# Main_SCH.net
KiCad netlist of a schematic drawn in Altium Designer
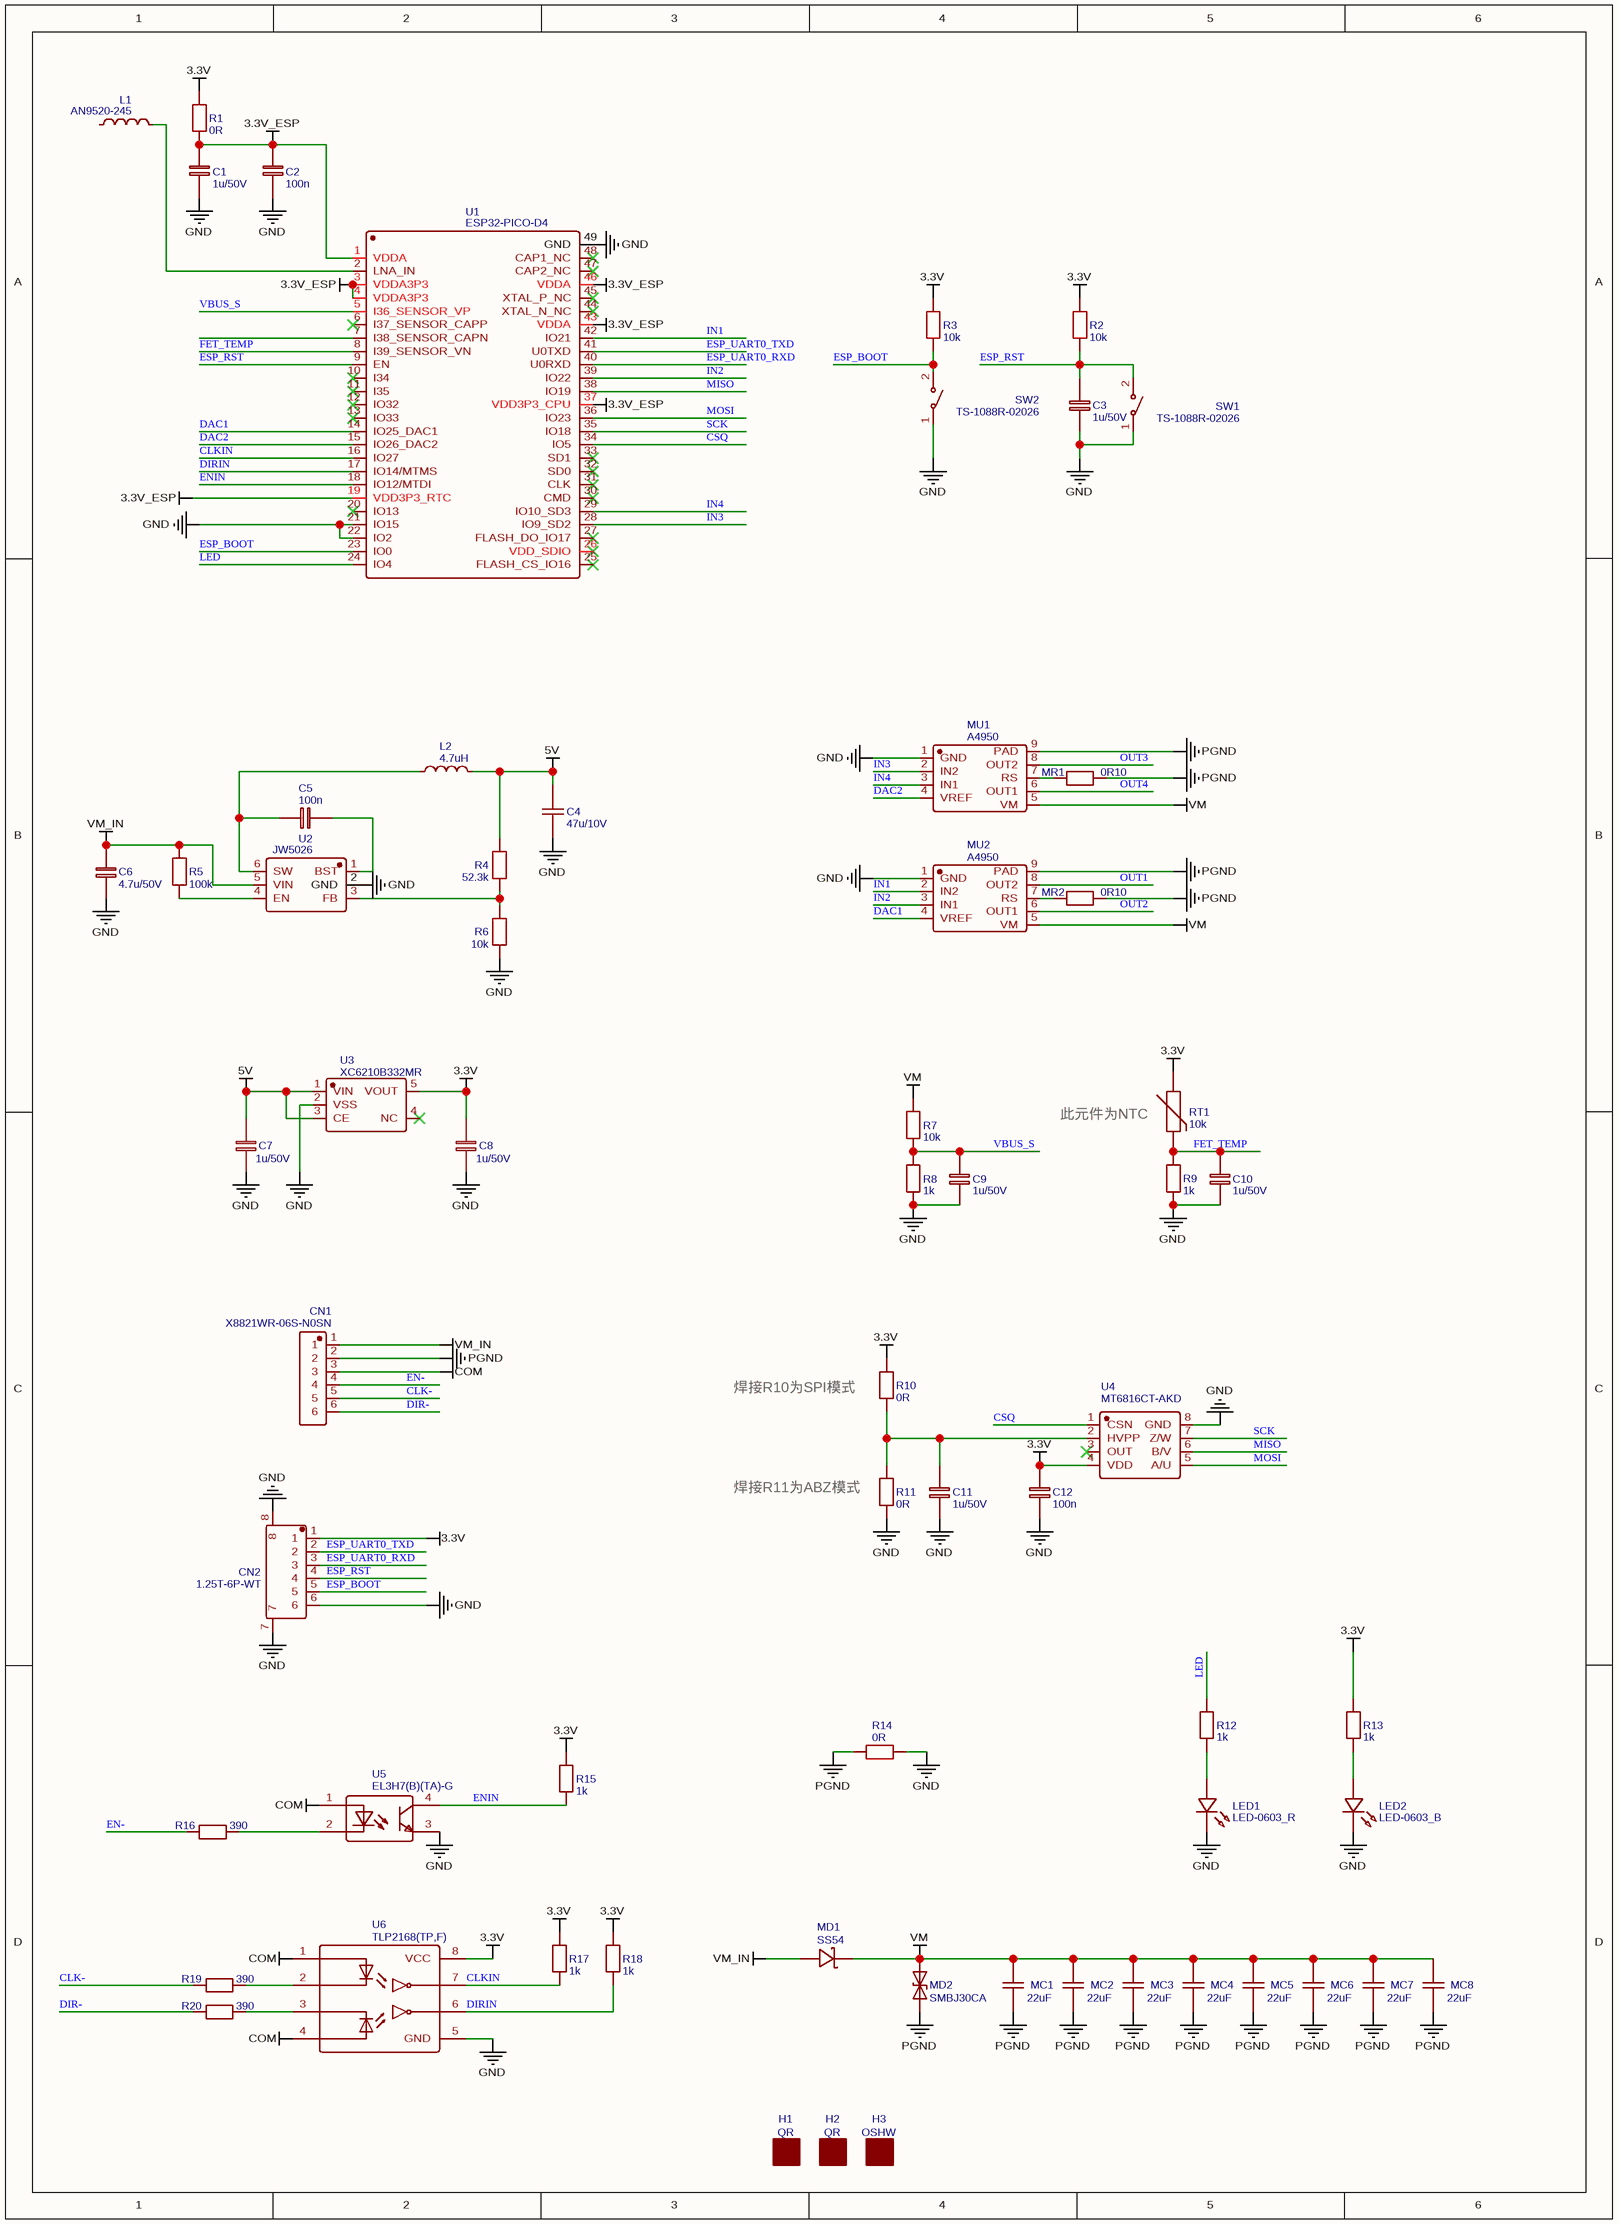
[diagram p0: Main SCH.schdoc]

(export (version "E")
  (design (tool "Eeschema 10.0.6"))
  (components
    (comp (ref "C1")
      (value "1u/50V")
      (fields
        (field (name "BOM_MANUFACTURER PART") "CL10A105KB8NNNC")
        (field (name "BOM_SUPPLIER PART") "C15849")
      )
      (libsource (lib "altium-import") (part "root_0_1u/50V_"))
    )
    (comp (ref "C2")
      (value "100n")
      (fields
        (field (name "BOM_MANUFACTURER PART") "CC0603KRX7R9BB104")
        (field (name "BOM_SUPPLIER PART") "C14663")
      )
      (libsource (lib "altium-import") (part "root_0_100n_"))
    )
    (comp (ref "C3")
      (value "1u/50V")
      (fields
        (field (name "BOM_MANUFACTURER PART") "CL10A105KB8NNNC")
        (field (name "BOM_SUPPLIER PART") "C15849")
      )
      (libsource (lib "altium-import") (part "root_2_1u/50V_"))
    )
    (comp (ref "C4")
      (value "47u/10V")
      (fields
        (field (name "BOM_SUPPLIER PART") "C96123")
        (field (name "BOM_MANUFACTURER PART") "CL31A476MPHNNNE")
        (field (name "CONTRIBUTOR") "LCSC")
      )
      (libsource (lib "altium-import") (part "root_0_47u/10V_"))
    )
    (comp (ref "C5")
      (value "100n")
      (fields
        (field (name "BOM_MANUFACTURER PART") "CC0603KRX7R9BB104")
        (field (name "BOM_SUPPLIER PART") "C14663")
      )
      (libsource (lib "altium-import") (part "root_1_100n_"))
    )
    (comp (ref "C6")
      (value "4.7u/50V")
      (fields
        (field (name "BOM_MANUFACTURER PART") "12065C475KAT4A")
        (field (name "BOM_SUPPLIER PART") "C141667")
      )
      (libsource (lib "altium-import") (part "root_2_4.7u/50V_"))
    )
    (comp (ref "C7")
      (value "1u/50V")
      (fields
        (field (name "BOM_SUPPLIER PART") "C15849")
        (field (name "BOM_MANUFACTURER PART") "CL10A105KB8NNNC")
        (field (name "CONTRIBUTOR") "LCEDA_Lib")
      )
      (libsource (lib "altium-import") (part "root_1_1u/50V_"))
    )
    (comp (ref "C8")
      (value "1u/50V")
      (fields
        (field (name "BOM_SUPPLIER PART") "C15849")
        (field (name "BOM_MANUFACTURER PART") "CL10A105KB8NNNC")
        (field (name "CONTRIBUTOR") "LCEDA_Lib")
      )
      (libsource (lib "altium-import") (part "root_1_1u/50V_"))
    )
    (comp (ref "C9")
      (value "1u/50V")
      (fields
        (field (name "BOM_MANUFACTURER PART") "CL10A105KB8NNNC")
        (field (name "BOM_SUPPLIER PART") "C15849")
      )
      (libsource (lib "altium-import") (part "root_2_1u/50V_"))
    )
    (comp (ref "C10")
      (value "1u/50V")
      (fields
        (field (name "BOM_MANUFACTURER PART") "CL10A105KB8NNNC")
        (field (name "BOM_SUPPLIER PART") "C15849")
      )
      (libsource (lib "altium-import") (part "root_2_1u/50V_"))
    )
    (comp (ref "C11")
      (value "1u/50V")
      (fields
        (field (name "BOM_MANUFACTURER PART") "CL10A105KB8NNNC")
        (field (name "BOM_SUPPLIER PART") "C15849")
      )
      (libsource (lib "altium-import") (part "root_2_1u/50V_"))
    )
    (comp (ref "C12")
      (value "100n")
      (fields
        (field (name "BOM_MANUFACTURER PART") "CC0603KRX7R9BB104")
        (field (name "BOM_SUPPLIER PART") "C14663")
      )
      (libsource (lib "altium-import") (part "root_2_100n_"))
    )
    (comp (ref "CN1")
      (value "X8821WR-06S-N0SN")
      (fields (field (name "BOM_SUPPLIER PART") "C388743") (field (name "CONTRIBUTOR") "LCSC"))
      (libsource (lib "altium-import") (part "root_0_X8821WR-06S-N0SN_"))
    )
    (comp (ref "CN2")
      (value "1.25T-6P-WT")
      (fields (field (name "BOM_SUPPLIER PART") "C97377"))
      (libsource (lib "altium-import") (part "root_0_1.25T-6P-WT_"))
    )
    (comp (ref "H1")
      (value "QR")
      (fields (field (name "CONTRIBUTOR") "snrqcf"))
      (libsource (lib "altium-import") (part "root_0_QR_"))
    )
    (comp (ref "H2")
      (value "QR")
      (fields (field (name "CONTRIBUTOR") "snrqcf"))
      (libsource (lib "altium-import") (part "root_0_QR_"))
    )
    (comp (ref "H3")
      (value "OSHW")
      (fields (field (name "CONTRIBUTOR") "snrqcf"))
      (libsource (lib "altium-import") (part "root_0_OSHW_"))
    )
    (comp (ref "L1")
      (value "AN9520-245")
      (fields (field (name "BOM_SUPPLIER PART") "C99665"))
      (libsource (lib "altium-import") (part "root_0_AN9520-245_"))
    )
    (comp (ref "L2")
      (value "4.7uH")
      (fields
        (field (name "BOM_SUPPLIER PART") "C490449")
        (field (name "BOM_MANUFACTURER PART") "MPIH252010-4R7M-LF")
        (field (name "CONTRIBUTOR") "LCSC")
      )
      (libsource (lib "altium-import") (part "root_0_4.7uH_"))
    )
    (comp (ref "LED1")
      (value "LED-0603_R")
      (fields
        (field (name "BOM_MANUFACTURER PART") "19-217/R6C-AL1M2VY/3T")
        (field (name "BOM_SUPPLIER PART") "C72044")
        (field (name "CONTRIBUTOR") "LCEDA_01")
      )
      (libsource (lib "altium-import") (part "root_3_LED-0603_R_"))
    )
    (comp (ref "LED2")
      (value "LED-0603_B")
      (fields
        (field (name "BOM_MANUFACTURER PART") "19-217/BHC-ZL1M2RY/3T")
        (field (name "BOM_SUPPLIER PART") "C72041")
        (field (name "CONTRIBUTOR") "LCEDA_01")
      )
      (libsource (lib "altium-import") (part "root_3_LED-0603_B_"))
    )
    (comp (ref "MC1")
      (value "22uF")
      (fields (field (name "BOM_SUPPLIER PART") "C171750") (field (name "CONTRIBUTOR") "LCSC"))
      (libsource (lib "altium-import") (part "root_0_22uF_"))
    )
    (comp (ref "MC2")
      (value "22uF")
      (fields (field (name "BOM_SUPPLIER PART") "C171750") (field (name "CONTRIBUTOR") "LCSC"))
      (libsource (lib "altium-import") (part "root_0_22uF_"))
    )
    (comp (ref "MC3")
      (value "22uF")
      (fields (field (name "BOM_SUPPLIER PART") "C171750") (field (name "CONTRIBUTOR") "LCSC"))
      (libsource (lib "altium-import") (part "root_0_22uF_"))
    )
    (comp (ref "MC4")
      (value "22uF")
      (fields (field (name "BOM_SUPPLIER PART") "C171750") (field (name "CONTRIBUTOR") "LCSC"))
      (libsource (lib "altium-import") (part "root_0_22uF_"))
    )
    (comp (ref "MC5")
      (value "22uF")
      (fields (field (name "BOM_SUPPLIER PART") "C171750") (field (name "CONTRIBUTOR") "LCSC"))
      (libsource (lib "altium-import") (part "root_0_22uF_"))
    )
    (comp (ref "MC6")
      (value "22uF")
      (fields (field (name "BOM_SUPPLIER PART") "C171750") (field (name "CONTRIBUTOR") "LCSC"))
      (libsource (lib "altium-import") (part "root_0_22uF_"))
    )
    (comp (ref "MC7")
      (value "22uF")
      (fields (field (name "BOM_SUPPLIER PART") "C171750") (field (name "CONTRIBUTOR") "LCSC"))
      (libsource (lib "altium-import") (part "root_0_22uF_"))
    )
    (comp (ref "MC8")
      (value "22uF")
      (fields (field (name "BOM_SUPPLIER PART") "C171750") (field (name "CONTRIBUTOR") "LCSC"))
      (libsource (lib "altium-import") (part "root_0_22uF_"))
    )
    (comp (ref "MD1")
      (value "SS54")
      (fields (field (name "BOM_SUPPLIER PART") "C32513"))
      (libsource (lib "altium-import") (part "root_2_SS54_"))
    )
    (comp (ref "MD2")
      (value "SMBJ30CA")
      (fields (field (name "BOM_MANUFACTURER PART") "SMBJ15CA") (field (name "BOM_SUPPLIER PART") "C362083"))
      (libsource (lib "altium-import") (part "root_1_SMBJ30CA_"))
    )
    (comp (ref "MR1")
      (value "0R10")
      (fields
        (field (name "BOM_SUPPLIER PART") "C388443")
        (field (name "BOM_MANUFACTURER PART") "STE1206A1W0R100F")
        (field (name "CONTRIBUTOR") "LCEDA_Lib")
      )
      (libsource (lib "altium-import") (part "root_0_0R10_"))
    )
    (comp (ref "MR2")
      (value "0R10")
      (fields
        (field (name "BOM_SUPPLIER PART") "C388443")
        (field (name "BOM_MANUFACTURER PART") "STE1206A1W0R100F")
        (field (name "CONTRIBUTOR") "LCEDA_Lib")
      )
      (libsource (lib "altium-import") (part "root_0_0R10_"))
    )
    (comp (ref "MU1")
      (value "A4950")
      (fields
        (field (name "BOM_MANUFACTURER PART") "A4950ELJTR-T")
        (field (name "BOM_SUPPLIER PART") "C82404")
        (field (name "CONTRIBUTOR") "矛盾聚合体")
      )
      (libsource (lib "altium-import") (part "root_0_A4950_"))
    )
    (comp (ref "MU2")
      (value "A4950")
      (fields
        (field (name "BOM_MANUFACTURER PART") "A4950ELJTR-T")
        (field (name "BOM_SUPPLIER PART") "C82404")
        (field (name "CONTRIBUTOR") "矛盾聚合体")
      )
      (libsource (lib "altium-import") (part "root_0_A4950_"))
    )
    (comp (ref "R1")
      (value "0R")
      (fields
        (field (name "BOM_MANUFACTURER PART") "0603WAJ0000T5E")
        (field (name "BOM_SUPPLIER PART") "C15402")
      )
      (libsource (lib "altium-import") (part "root_3_0R_"))
    )
    (comp (ref "R2")
      (value "10k")
      (fields
        (field (name "BOM_SUPPLIER PART") "C25804")
        (field (name "BOM_MANUFACTURER PART") "0603WAF1002T5E")
        (field (name "CONTRIBUTOR") "LCEDA_Lib")
      )
      (libsource (lib "altium-import") (part "root_3_10k_"))
    )
    (comp (ref "R3")
      (value "10k")
      (fields
        (field (name "BOM_SUPPLIER PART") "C25804")
        (field (name "BOM_MANUFACTURER PART") "0603WAF1002T5E")
        (field (name "CONTRIBUTOR") "LCEDA_Lib")
      )
      (libsource (lib "altium-import") (part "root_3_10k_"))
    )
    (comp (ref "R4")
      (value "52.3k")
      (fields
        (field (name "BOM_MANUFACTURER PART") "0603WAF5232T5E")
        (field (name "BOM_SUPPLIER PART") "C23198")
      )
      (libsource (lib "altium-import") (part "root_3_52.3k_"))
    )
    (comp (ref "R5")
      (value "100k")
      (fields
        (field (name "BOM_MANUFACTURER PART") "0603WAF1002T5E")
        (field (name "BOM_SUPPLIER PART") "C25804")
      )
      (libsource (lib "altium-import") (part "root_3_100k_"))
    )
    (comp (ref "R6")
      (value "10k")
      (fields
        (field (name "BOM_MANUFACTURER PART") "0603WAF1002T5E")
        (field (name "BOM_SUPPLIER PART") "C25804")
      )
      (libsource (lib "altium-import") (part "root_3_10k_"))
    )
    (comp (ref "R7")
      (value "10k")
      (fields
        (field (name "BOM_SUPPLIER PART") "C25804")
        (field (name "BOM_MANUFACTURER PART") "0603WAF1002T5E")
        (field (name "CONTRIBUTOR") "LCEDA_Lib")
      )
      (libsource (lib "altium-import") (part "root_3_10k_"))
    )
    (comp (ref "R8")
      (value "1k")
      (fields
        (field (name "BOM_SUPPLIER PART") "C21190")
        (field (name "BOM_MANUFACTURER PART") "0603WAF1001T5E")
        (field (name "CONTRIBUTOR") "LCEDA_Lib")
      )
      (libsource (lib "altium-import") (part "root_3_1k_"))
    )
    (comp (ref "R9")
      (value "1k")
      (fields
        (field (name "BOM_MANUFACTURER PART") "0603WAF1001T5E")
        (field (name "BOM_SUPPLIER PART") "C21190")
      )
      (libsource (lib "altium-import") (part "root_3_1k_"))
    )
    (comp (ref "R10")
      (value "0R")
      (fields
        (field (name "BOM_SUPPLIER PART") "C15402")
        (field (name "BOM_MANUFACTURER PART") "0603WAJ0000T5E")
        (field (name "CONTRIBUTOR") "LCEDA_Lib")
      )
      (libsource (lib "altium-import") (part "root_3_0R_"))
    )
    (comp (ref "R11")
      (value "0R")
      (fields
        (field (name "BOM_SUPPLIER PART") "C15402")
        (field (name "BOM_MANUFACTURER PART") "0603WAJ0000T5E")
        (field (name "CONTRIBUTOR") "LCEDA_Lib")
      )
      (libsource (lib "altium-import") (part "root_3_0R_"))
    )
    (comp (ref "R12")
      (value "1k")
      (fields
        (field (name "BOM_MANUFACTURER PART") "0603WAF1001T5E")
        (field (name "BOM_SUPPLIER PART") "C21190")
      )
      (libsource (lib "altium-import") (part "root_3_1k_"))
    )
    (comp (ref "R13")
      (value "1k")
      (fields
        (field (name "BOM_MANUFACTURER PART") "0603WAF1001T5E")
        (field (name "BOM_SUPPLIER PART") "C21190")
      )
      (libsource (lib "altium-import") (part "root_3_1k_"))
    )
    (comp (ref "R14")
      (value "0R")
      (fields
        (field (name "BOM_MANUFACTURER PART") "0603WAJ0000T5E")
        (field (name "BOM_SUPPLIER PART") "C15402")
      )
      (libsource (lib "altium-import") (part "root_0_0R_"))
    )
    (comp (ref "R15")
      (value "1k")
      (fields
        (field (name "BOM_SUPPLIER PART") "C21190")
        (field (name "BOM_MANUFACTURER PART") "0603WAF1001T5E")
        (field (name "CONTRIBUTOR") "LCEDA_Lib")
      )
      (libsource (lib "altium-import") (part "root_3_1k_"))
    )
    (comp (ref "R16")
      (value "390")
      (fields
        (field (name "BOM_SUPPLIER PART") "C23151")
        (field (name "BOM_MANUFACTURER PART") "0603WAF3900T5E")
        (field (name "CONTRIBUTOR") "LCEDA_Lib")
      )
      (libsource (lib "altium-import") (part "root_2_390_"))
    )
    (comp (ref "R17")
      (value "1k")
      (fields
        (field (name "BOM_SUPPLIER PART") "C21190")
        (field (name "BOM_MANUFACTURER PART") "0603WAF1001T5E")
        (field (name "CONTRIBUTOR") "LCEDA_Lib")
      )
      (libsource (lib "altium-import") (part "root_3_1k_"))
    )
    (comp (ref "R18")
      (value "1k")
      (fields
        (field (name "BOM_SUPPLIER PART") "C21190")
        (field (name "BOM_MANUFACTURER PART") "0603WAF1001T5E")
        (field (name "CONTRIBUTOR") "LCEDA_Lib")
      )
      (libsource (lib "altium-import") (part "root_3_1k_"))
    )
    (comp (ref "R19")
      (value "390")
      (fields
        (field (name "BOM_SUPPLIER PART") "C23151")
        (field (name "BOM_MANUFACTURER PART") "0603WAF3900T5E")
        (field (name "CONTRIBUTOR") "LCEDA_Lib")
      )
      (libsource (lib "altium-import") (part "root_2_390_"))
    )
    (comp (ref "R20")
      (value "390")
      (fields
        (field (name "BOM_SUPPLIER PART") "C23151")
        (field (name "BOM_MANUFACTURER PART") "0603WAF3900T5E")
        (field (name "CONTRIBUTOR") "LCEDA_Lib")
      )
      (libsource (lib "altium-import") (part "root_2_390_"))
    )
    (comp (ref "RT1")
      (value "10k")
      (fields
        (field (name "BOM_SUPPLIER PART") "C524451")
        (field (name "BOM_MANUFACTURER PART") "NTCG164BH103JT1")
        (field (name "CONTRIBUTOR") "LCSC")
      )
      (libsource (lib "altium-import") (part "root_1_10k_"))
    )
    (comp (ref "SW1")
      (value "TS-1088R-02026")
      (fields (field (name "BOM_SUPPLIER PART") "C455280") (field (name "CONTRIBUTOR") "LCSC"))
      (libsource (lib "altium-import") (part "root_1_TS-1088R-02026_"))
    )
    (comp (ref "SW2")
      (value "TS-1088R-02026")
      (fields (field (name "BOM_SUPPLIER PART") "C455280") (field (name "CONTRIBUTOR") "LCSC"))
      (libsource (lib "altium-import") (part "root_1_TS-1088R-02026_"))
    )
    (comp (ref "U1")
      (value "ESP32-PICO-D4")
      (fields (field (name "BOM_SUPPLIER PART") "C193707") (field (name "CONTRIBUTOR") "LCSC"))
      (libsource (lib "altium-import") (part "root_0_ESP32-PICO-D4_"))
    )
    (comp (ref "U2")
      (value "JW5026")
      (fields (field (name "BOM_SUPPLIER PART") "C185109") (field (name "CONTRIBUTOR") "LCSC"))
      (libsource (lib "altium-import") (part "root_0_JW5026_"))
    )
    (comp (ref "U3")
      (value "XC6210B332MR")
      (fields (field (name "BOM_SUPPLIER PART") "C424705") (field (name "CONTRIBUTOR") "LCSC"))
      (libsource (lib "altium-import") (part "root_0_XC6210B332MR_"))
    )
    (comp (ref "U4")
      (value "MT6816CT-AKD")
      (fields (field (name "BOM_SUPPLIER PART") "C879561") (field (name "CONTRIBUTOR") "LCSC"))
      (libsource (lib "altium-import") (part "root_0_MT6816CT-AKD_"))
    )
    (comp (ref "U5")
      (value "EL3H7(B)(TA)-G")
      (fields (field (name "BOM_SUPPLIER PART") "C32565"))
      (libsource (lib "altium-import") (part "root_0_EL3H7(B)(TA)-G_"))
    )
    (comp (ref "U6")
      (value "TLP2168(TP,F)")
      (fields (field (name "BOM_SUPPLIER PART") "C99480") (field (name "CONTRIBUTOR") "LCSC"))
      (libsource (lib "altium-import") (part "root_0_TLP2168(TP,F)_"))
    )
  )
  (nets
    (net (code "1") (name "/CLK-") (class "Default")
      (node (ref "CN1") (pin "5") (pinfunction "5_5") (pintype "passive"))
      (node (ref "R19") (pin "2") (pinfunction "2_2") (pintype "passive"))
    )
    (net (code "2") (name "/CLKIN") (class "Default")
      (node (ref "R17") (pin "2") (pinfunction "2_2") (pintype "passive"))
      (node (ref "U1") (pin "16") (pinfunction "IO27_16") (pintype "passive"))
      (node (ref "U6") (pin "7") (pinfunction "VO1_7") (pintype "passive"))
    )
    (net (code "3") (name "/CSQ") (class "Default")
      (node (ref "U1") (pin "34") (pinfunction "IO5_34") (pintype "passive"))
      (node (ref "U4") (pin "1") (pinfunction "CSN_1") (pintype "passive"))
    )
    (net (code "4") (name "/DAC1") (class "Default")
      (node (ref "MU2") (pin "4") (pinfunction "VREF_4") (pintype "passive"))
      (node (ref "U1") (pin "14") (pinfunction "IO25_DAC1_14") (pintype "passive"))
    )
    (net (code "5") (name "/DAC2") (class "Default")
      (node (ref "MU1") (pin "4") (pinfunction "VREF_4") (pintype "passive"))
      (node (ref "U1") (pin "15") (pinfunction "IO26_DAC2_15") (pintype "passive"))
    )
    (net (code "6") (name "/DIR-") (class "Default")
      (node (ref "CN1") (pin "6") (pinfunction "6_6") (pintype "passive"))
      (node (ref "R20") (pin "2") (pinfunction "2_2") (pintype "passive"))
    )
    (net (code "7") (name "/DIRIN") (class "Default")
      (node (ref "R18") (pin "2") (pinfunction "2_2") (pintype "passive"))
      (node (ref "U1") (pin "17") (pinfunction "IO14/MTMS_17") (pintype "passive"))
      (node (ref "U6") (pin "6") (pinfunction "VO2_6") (pintype "passive"))
    )
    (net (code "8") (name "/EN-") (class "Default")
      (node (ref "CN1") (pin "4") (pinfunction "4_4") (pintype "passive"))
      (node (ref "R16") (pin "2") (pinfunction "2_2") (pintype "passive"))
    )
    (net (code "9") (name "/ENIN") (class "Default")
      (node (ref "R15") (pin "2") (pinfunction "2_2") (pintype "passive"))
      (node (ref "U1") (pin "18") (pinfunction "IO12/MTDI_18") (pintype "passive"))
      (node (ref "U5") (pin "4") (pinfunction "COL_4") (pintype "passive"))
    )
    (net (code "10") (name "/ESP_BOOT") (class "Default")
      (node (ref "CN2") (pin "5") (pinfunction "5_5") (pintype "passive"))
      (node (ref "R3") (pin "2") (pinfunction "2_2") (pintype "passive"))
      (node (ref "SW2") (pin "2") (pinfunction "2_2") (pintype "passive"))
      (node (ref "U1") (pin "23") (pinfunction "IO0_23") (pintype "passive"))
    )
    (net (code "11") (name "/ESP_RST") (class "Default")
      (node (ref "C3") (pin "2") (pinfunction "2_2") (pintype "passive"))
      (node (ref "CN2") (pin "4") (pinfunction "4_4") (pintype "passive"))
      (node (ref "R2") (pin "2") (pinfunction "2_2") (pintype "passive"))
      (node (ref "SW1") (pin "2") (pinfunction "2_2") (pintype "passive"))
      (node (ref "U1") (pin "9") (pinfunction "EN_9") (pintype "passive"))
    )
    (net (code "12") (name "/ESP_UART0_RXD") (class "Default")
      (node (ref "CN2") (pin "3") (pinfunction "3_3") (pintype "passive"))
      (node (ref "U1") (pin "40") (pinfunction "U0RXD_40") (pintype "passive"))
    )
    (net (code "13") (name "/ESP_UART0_TXD") (class "Default")
      (node (ref "CN2") (pin "2") (pinfunction "2_2") (pintype "passive"))
      (node (ref "U1") (pin "41") (pinfunction "U0TXD_41") (pintype "passive"))
    )
    (net (code "14") (name "/FET_TEMP") (class "Default")
      (node (ref "C10") (pin "2") (pinfunction "2_2") (pintype "passive"))
      (node (ref "R9") (pin "1") (pinfunction "1_1") (pintype "passive"))
      (node (ref "RT1") (pin "1") (pinfunction "1_1") (pintype "passive"))
      (node (ref "U1") (pin "8") (pinfunction "I39_SENSOR_VN_8") (pintype "passive"))
    )
    (net (code "15") (name "/IN1") (class "Default")
      (node (ref "MU2") (pin "2") (pinfunction "IN2_2") (pintype "passive"))
      (node (ref "U1") (pin "42") (pinfunction "IO21_42") (pintype "passive"))
    )
    (net (code "16") (name "/IN2") (class "Default")
      (node (ref "MU2") (pin "3") (pinfunction "IN1_3") (pintype "passive"))
      (node (ref "U1") (pin "39") (pinfunction "IO22_39") (pintype "passive"))
    )
    (net (code "17") (name "/IN3") (class "Default")
      (node (ref "MU1") (pin "2") (pinfunction "IN2_2") (pintype "passive"))
      (node (ref "U1") (pin "28") (pinfunction "IO9_SD2_28") (pintype "passive"))
    )
    (net (code "18") (name "/IN4") (class "Default")
      (node (ref "MU1") (pin "3") (pinfunction "IN1_3") (pintype "passive"))
      (node (ref "U1") (pin "29") (pinfunction "IO10_SD3_29") (pintype "passive"))
    )
    (net (code "19") (name "/LED") (class "Default")
      (node (ref "R12") (pin "1") (pinfunction "1_1") (pintype "passive"))
      (node (ref "U1") (pin "24") (pinfunction "IO4_24") (pintype "passive"))
    )
    (net (code "20") (name "/MISO") (class "Default")
      (node (ref "U1") (pin "38") (pinfunction "IO19_38") (pintype "passive"))
      (node (ref "U4") (pin "6") (pinfunction "B/V_6") (pintype "passive"))
    )
    (net (code "21") (name "/MOSI") (class "Default")
      (node (ref "U1") (pin "36") (pinfunction "IO23_36") (pintype "passive"))
      (node (ref "U4") (pin "5") (pinfunction "A/U_5") (pintype "passive"))
    )
    (net (code "22") (name "/OUT1") (class "Default")
      (node (ref "MU2") (pin "8") (pinfunction "OUT2_8") (pintype "passive"))
    )
    (net (code "23") (name "/OUT2") (class "Default")
      (node (ref "MU2") (pin "6") (pinfunction "OUT1_6") (pintype "passive"))
    )
    (net (code "24") (name "/OUT3") (class "Default")
      (node (ref "MU1") (pin "8") (pinfunction "OUT2_8") (pintype "passive"))
    )
    (net (code "25") (name "/OUT4") (class "Default")
      (node (ref "MU1") (pin "6") (pinfunction "OUT1_6") (pintype "passive"))
    )
    (net (code "26") (name "/SCK") (class "Default")
      (node (ref "U1") (pin "35") (pinfunction "IO18_35") (pintype "passive"))
      (node (ref "U4") (pin "7") (pinfunction "Z/W_7") (pintype "passive"))
    )
    (net (code "27") (name "/VBUS_S") (class "Default")
      (node (ref "C9") (pin "2") (pinfunction "2_2") (pintype "passive"))
      (node (ref "R7") (pin "2") (pinfunction "2_2") (pintype "passive"))
      (node (ref "R8") (pin "1") (pinfunction "1_1") (pintype "passive"))
      (node (ref "U1") (pin "5") (pinfunction "I36_SENSOR_VP_5") (pintype "passive"))
    )
    (net (code "28") (name "3.3V") (class "Default")
      (node (ref "C12") (pin "2") (pinfunction "2_2") (pintype "passive"))
      (node (ref "C8") (pin "2") (pinfunction "2_2") (pintype "passive"))
      (node (ref "CN2") (pin "1") (pinfunction "1_1") (pintype "passive"))
      (node (ref "R1") (pin "1") (pinfunction "1_1") (pintype "passive"))
      (node (ref "R10") (pin "1") (pinfunction "1_1") (pintype "passive"))
      (node (ref "R13") (pin "1") (pinfunction "1_1") (pintype "passive"))
      (node (ref "R15") (pin "1") (pinfunction "1_1") (pintype "passive"))
      (node (ref "R17") (pin "1") (pinfunction "1_1") (pintype "passive"))
      (node (ref "R18") (pin "1") (pinfunction "1_1") (pintype "passive"))
      (node (ref "R2") (pin "1") (pinfunction "1_1") (pintype "passive"))
      (node (ref "R3") (pin "1") (pinfunction "1_1") (pintype "passive"))
      (node (ref "RT1") (pin "2") (pinfunction "2_2") (pintype "passive"))
      (node (ref "U3") (pin "5") (pinfunction "VOUT_5") (pintype "passive"))
      (node (ref "U4") (pin "4") (pinfunction "VDD_4") (pintype "passive"))
      (node (ref "U6") (pin "8") (pinfunction "VCC_8") (pintype "passive"))
    )
    (net (code "29") (name "3.3V_ESP") (class "Default")
      (node (ref "C1") (pin "1") (pinfunction "1_1") (pintype "passive"))
      (node (ref "C2") (pin "1") (pinfunction "1_1") (pintype "passive"))
      (node (ref "R1") (pin "2") (pinfunction "2_2") (pintype "passive"))
      (node (ref "U1") (pin "1") (pinfunction "VDDA_1") (pintype "passive"))
      (node (ref "U1") (pin "19") (pinfunction "VDD3P3_RTC_19") (pintype "passive"))
      (node (ref "U1") (pin "3") (pinfunction "VDDA3P3_3") (pintype "passive"))
      (node (ref "U1") (pin "37") (pinfunction "VDD3P3_CPU_37") (pintype "passive"))
      (node (ref "U1") (pin "4") (pinfunction "VDDA3P3_4") (pintype "passive"))
      (node (ref "U1") (pin "43") (pinfunction "VDDA_43") (pintype "passive"))
      (node (ref "U1") (pin "46") (pinfunction "VDDA_46") (pintype "passive"))
    )
    (net (code "30") (name "5V") (class "Default")
      (node (ref "C4") (pin "2") (pinfunction "2_2") (pintype "passive"))
      (node (ref "C7") (pin "2") (pinfunction "2_2") (pintype "passive"))
      (node (ref "L2") (pin "2") (pinfunction "2_2") (pintype "passive"))
      (node (ref "R4") (pin "1") (pinfunction "1_1") (pintype "passive"))
      (node (ref "U3") (pin "1") (pinfunction "VIN_1") (pintype "passive"))
      (node (ref "U3") (pin "3") (pinfunction "CE_3") (pintype "passive"))
    )
    (net (code "31") (name "COM") (class "Default")
      (node (ref "CN1") (pin "3") (pinfunction "3_3") (pintype "passive"))
      (node (ref "U5") (pin "1") (pinfunction "AN_1") (pintype "passive"))
      (node (ref "U6") (pin "1") (pinfunction "AN1_1") (pintype "passive"))
      (node (ref "U6") (pin "4") (pinfunction "AN2_4") (pintype "passive"))
    )
    (net (code "32") (name "GND") (class "Default")
      (node (ref "C1") (pin "2") (pinfunction "2_2") (pintype "passive"))
      (node (ref "C10") (pin "1") (pinfunction "1_1") (pintype "passive"))
      (node (ref "C11") (pin "1") (pinfunction "1_1") (pintype "passive"))
      (node (ref "C12") (pin "1") (pinfunction "1_1") (pintype "passive"))
      (node (ref "C2") (pin "2") (pinfunction "2_2") (pintype "passive"))
      (node (ref "C3") (pin "1") (pinfunction "1_1") (pintype "passive"))
      (node (ref "C4") (pin "1") (pinfunction "1_1") (pintype "passive"))
      (node (ref "C6") (pin "1") (pinfunction "1_1") (pintype "passive"))
      (node (ref "C7") (pin "1") (pinfunction "1_1") (pintype "passive"))
      (node (ref "C8") (pin "1") (pinfunction "1_1") (pintype "passive"))
      (node (ref "C9") (pin "1") (pinfunction "1_1") (pintype "passive"))
      (node (ref "CN2") (pin "6") (pinfunction "6_6") (pintype "passive"))
      (node (ref "CN2") (pin "7") (pinfunction "7_7") (pintype "passive"))
      (node (ref "CN2") (pin "8") (pinfunction "8_8") (pintype "passive"))
      (node (ref "LED1") (pin "2") (pinfunction "2_2") (pintype "passive"))
      (node (ref "LED2") (pin "2") (pinfunction "2_2") (pintype "passive"))
      (node (ref "MU1") (pin "1") (pinfunction "GND_1") (pintype "passive"))
      (node (ref "MU2") (pin "1") (pinfunction "GND_1") (pintype "passive"))
      (node (ref "R11") (pin "2") (pinfunction "2_2") (pintype "passive"))
      (node (ref "R14") (pin "2") (pinfunction "2_2") (pintype "passive"))
      (node (ref "R6") (pin "2") (pinfunction "2_2") (pintype "passive"))
      (node (ref "R8") (pin "2") (pinfunction "2_2") (pintype "passive"))
      (node (ref "R9") (pin "2") (pinfunction "2_2") (pintype "passive"))
      (node (ref "SW1") (pin "1") (pinfunction "1_1") (pintype "passive"))
      (node (ref "SW2") (pin "1") (pinfunction "1_1") (pintype "passive"))
      (node (ref "U1") (pin "21") (pinfunction "IO15_21") (pintype "passive"))
      (node (ref "U1") (pin "22") (pinfunction "IO2_22") (pintype "passive"))
      (node (ref "U1") (pin "49") (pinfunction "GND_49") (pintype "passive"))
      (node (ref "U2") (pin "2") (pinfunction "GND_2") (pintype "passive"))
      (node (ref "U3") (pin "2") (pinfunction "VSS_2") (pintype "passive"))
      (node (ref "U4") (pin "8") (pinfunction "GND_8") (pintype "passive"))
      (node (ref "U5") (pin "3") (pinfunction "EM_3") (pintype "passive"))
      (node (ref "U6") (pin "5") (pinfunction "GND_5") (pintype "passive"))
    )
    (net (code "33") (name "Net-(LED1-Pad1)") (class "Default")
      (node (ref "LED1") (pin "1") (pinfunction "1_1") (pintype "passive"))
      (node (ref "R12") (pin "2") (pinfunction "2_2") (pintype "passive"))
    )
    (net (code "34") (name "Net-(LED2-Pad1)") (class "Default")
      (node (ref "LED2") (pin "1") (pinfunction "1_1") (pintype "passive"))
      (node (ref "R13") (pin "2") (pinfunction "2_2") (pintype "passive"))
    )
    (net (code "35") (name "Net-(MU1-RS)") (class "Default")
      (node (ref "MR1") (pin "2") (pinfunction "2_2") (pintype "passive"))
      (node (ref "MU1") (pin "7") (pinfunction "RS_7") (pintype "passive"))
    )
    (net (code "36") (name "Net-(MU2-RS)") (class "Default")
      (node (ref "MR2") (pin "2") (pinfunction "2_2") (pintype "passive"))
      (node (ref "MU2") (pin "7") (pinfunction "RS_7") (pintype "passive"))
    )
    (net (code "37") (name "Net-(U1-LNA_IN)") (class "Default")
      (node (ref "L1") (pin "1") (pinfunction "1_1") (pintype "passive"))
      (node (ref "U1") (pin "2") (pinfunction "LNA_IN_2") (pintype "passive"))
    )
    (net (code "38") (name "Net-(U2-BST)") (class "Default")
      (node (ref "C5") (pin "2") (pinfunction "2_2") (pintype "passive"))
      (node (ref "U2") (pin "1") (pinfunction "BST_1") (pintype "passive"))
    )
    (net (code "39") (name "Net-(U2-EN)") (class "Default")
      (node (ref "R5") (pin "2") (pinfunction "2_2") (pintype "passive"))
      (node (ref "U2") (pin "4") (pinfunction "EN_4") (pintype "passive"))
    )
    (net (code "40") (name "Net-(U2-FB)") (class "Default")
      (node (ref "R4") (pin "2") (pinfunction "2_2") (pintype "passive"))
      (node (ref "R6") (pin "1") (pinfunction "1_1") (pintype "passive"))
      (node (ref "U2") (pin "3") (pinfunction "FB_3") (pintype "passive"))
    )
    (net (code "41") (name "Net-(U2-SW)") (class "Default")
      (node (ref "C5") (pin "1") (pinfunction "1_1") (pintype "passive"))
      (node (ref "L2") (pin "1") (pinfunction "1_1") (pintype "passive"))
      (node (ref "U2") (pin "6") (pinfunction "SW_6") (pintype "passive"))
    )
    (net (code "42") (name "Net-(U4-HVPP)") (class "Default")
      (node (ref "C11") (pin "2") (pinfunction "2_2") (pintype "passive"))
      (node (ref "R10") (pin "2") (pinfunction "2_2") (pintype "passive"))
      (node (ref "R11") (pin "1") (pinfunction "1_1") (pintype "passive"))
      (node (ref "U4") (pin "2") (pinfunction "HVPP_2") (pintype "passive"))
    )
    (net (code "43") (name "Net-(U5-CAT)") (class "Default")
      (node (ref "R16") (pin "1") (pinfunction "1_1") (pintype "passive"))
      (node (ref "U5") (pin "2") (pinfunction "CAT_2") (pintype "passive"))
    )
    (net (code "44") (name "Net-(U6-CAT1)") (class "Default")
      (node (ref "R19") (pin "1") (pinfunction "1_1") (pintype "passive"))
      (node (ref "U6") (pin "2") (pinfunction "CAT1_2") (pintype "passive"))
    )
    (net (code "45") (name "Net-(U6-CAT2)") (class "Default")
      (node (ref "R20") (pin "1") (pinfunction "1_1") (pintype "passive"))
      (node (ref "U6") (pin "3") (pinfunction "CAT2_3") (pintype "passive"))
    )
    (net (code "46") (name "PGND") (class "Default")
      (node (ref "CN1") (pin "2") (pinfunction "2_2") (pintype "passive"))
      (node (ref "MC1") (pin "1") (pinfunction "1_1") (pintype "passive"))
      (node (ref "MC2") (pin "1") (pinfunction "1_1") (pintype "passive"))
      (node (ref "MC3") (pin "1") (pinfunction "1_1") (pintype "passive"))
      (node (ref "MC4") (pin "1") (pinfunction "1_1") (pintype "passive"))
      (node (ref "MC5") (pin "1") (pinfunction "1_1") (pintype "passive"))
      (node (ref "MC6") (pin "1") (pinfunction "1_1") (pintype "passive"))
      (node (ref "MC7") (pin "1") (pinfunction "1_1") (pintype "passive"))
      (node (ref "MC8") (pin "1") (pinfunction "1_1") (pintype "passive"))
      (node (ref "MD2") (pin "2") (pinfunction "A_2") (pintype "passive"))
      (node (ref "MR1") (pin "1") (pinfunction "1_1") (pintype "passive"))
      (node (ref "MR2") (pin "1") (pinfunction "1_1") (pintype "passive"))
      (node (ref "MU1") (pin "9") (pinfunction "PAD_9") (pintype "passive"))
      (node (ref "MU2") (pin "9") (pinfunction "PAD_9") (pintype "passive"))
      (node (ref "R14") (pin "1") (pinfunction "1_1") (pintype "passive"))
    )
    (net (code "47") (name "VM") (class "Default")
      (node (ref "MC1") (pin "2") (pinfunction "2_2") (pintype "passive"))
      (node (ref "MC2") (pin "2") (pinfunction "2_2") (pintype "passive"))
      (node (ref "MC3") (pin "2") (pinfunction "2_2") (pintype "passive"))
      (node (ref "MC4") (pin "2") (pinfunction "2_2") (pintype "passive"))
      (node (ref "MC5") (pin "2") (pinfunction "2_2") (pintype "passive"))
      (node (ref "MC6") (pin "2") (pinfunction "2_2") (pintype "passive"))
      (node (ref "MC7") (pin "2") (pinfunction "2_2") (pintype "passive"))
      (node (ref "MC8") (pin "2") (pinfunction "2_2") (pintype "passive"))
      (node (ref "MD1") (pin "2") (pinfunction "K_2") (pintype "passive"))
      (node (ref "MD2") (pin "1") (pinfunction "K_1") (pintype "passive"))
      (node (ref "MU1") (pin "5") (pinfunction "VM_5") (pintype "passive"))
      (node (ref "MU2") (pin "5") (pinfunction "VM_5") (pintype "passive"))
      (node (ref "R7") (pin "1") (pinfunction "1_1") (pintype "passive"))
    )
    (net (code "48") (name "VM_IN") (class "Default")
      (node (ref "C6") (pin "2") (pinfunction "2_2") (pintype "passive"))
      (node (ref "CN1") (pin "1") (pinfunction "1_1") (pintype "passive"))
      (node (ref "MD1") (pin "1") (pinfunction "A_1") (pintype "passive"))
      (node (ref "R5") (pin "1") (pinfunction "1_1") (pintype "passive"))
      (node (ref "U2") (pin "5") (pinfunction "VIN_5") (pintype "passive"))
    )
    (net (code "49") (name "unconnected-(L1-Pad2)") (class "Default")
      (node (ref "L1") (pin "2") (pinfunction "2_2") (pintype "passive"))
    )
    (net (code "50") (name "unconnected-(U1-CAP1_NC-Pad48)") (class "Default")
      (node (ref "U1") (pin "48") (pinfunction "CAP1_NC_48") (pintype "passive+no_connect"))
    )
    (net (code "51") (name "unconnected-(U1-CAP2_NC-Pad47)") (class "Default")
      (node (ref "U1") (pin "47") (pinfunction "CAP2_NC_47") (pintype "passive+no_connect"))
    )
    (net (code "52") (name "unconnected-(U1-CLK-Pad31)") (class "Default")
      (node (ref "U1") (pin "31") (pinfunction "CLK_31") (pintype "passive+no_connect"))
    )
    (net (code "53") (name "unconnected-(U1-CMD-Pad30)") (class "Default")
      (node (ref "U1") (pin "30") (pinfunction "CMD_30") (pintype "passive+no_connect"))
    )
    (net (code "54") (name "unconnected-(U1-FLASH_CS_IO16-Pad25)") (class "Default")
      (node (ref "U1") (pin "25") (pinfunction "FLASH_CS_IO16_25") (pintype "passive+no_connect"))
    )
    (net (code "55") (name "unconnected-(U1-FLASH_DO_IO17-Pad27)") (class "Default")
      (node (ref "U1") (pin "27") (pinfunction "FLASH_DO_IO17_27") (pintype "passive+no_connect"))
    )
    (net (code "56") (name "unconnected-(U1-I34-Pad10)") (class "Default")
      (node (ref "U1") (pin "10") (pinfunction "I34_10") (pintype "passive+no_connect"))
    )
    (net (code "57") (name "unconnected-(U1-I35-Pad11)") (class "Default")
      (node (ref "U1") (pin "11") (pinfunction "I35_11") (pintype "passive+no_connect"))
    )
    (net (code "58") (name "unconnected-(U1-I37_SENSOR_CAPP-Pad6)") (class "Default")
      (node (ref "U1") (pin "6") (pinfunction "I37_SENSOR_CAPP_6") (pintype "passive+no_connect"))
    )
    (net (code "59") (name "unconnected-(U1-I38_SENSOR_CAPN-Pad7)") (class "Default")
      (node (ref "U1") (pin "7") (pinfunction "I38_SENSOR_CAPN_7") (pintype "passive"))
    )
    (net (code "60") (name "unconnected-(U1-IO13-Pad20)") (class "Default")
      (node (ref "U1") (pin "20") (pinfunction "IO13_20") (pintype "passive+no_connect"))
    )
    (net (code "61") (name "unconnected-(U1-IO32-Pad12)") (class "Default")
      (node (ref "U1") (pin "12") (pinfunction "IO32_12") (pintype "passive+no_connect"))
    )
    (net (code "62") (name "unconnected-(U1-IO33-Pad13)") (class "Default")
      (node (ref "U1") (pin "13") (pinfunction "IO33_13") (pintype "passive+no_connect"))
    )
    (net (code "63") (name "unconnected-(U1-SD0-Pad32)") (class "Default")
      (node (ref "U1") (pin "32") (pinfunction "SD0_32") (pintype "passive+no_connect"))
    )
    (net (code "64") (name "unconnected-(U1-SD1-Pad33)") (class "Default")
      (node (ref "U1") (pin "33") (pinfunction "SD1_33") (pintype "passive+no_connect"))
    )
    (net (code "65") (name "unconnected-(U1-VDD_SDIO-Pad26)") (class "Default")
      (node (ref "U1") (pin "26") (pinfunction "VDD_SDIO_26") (pintype "passive+no_connect"))
    )
    (net (code "66") (name "unconnected-(U1-XTAL_N_NC-Pad44)") (class "Default")
      (node (ref "U1") (pin "44") (pinfunction "XTAL_N_NC_44") (pintype "passive+no_connect"))
    )
    (net (code "67") (name "unconnected-(U1-XTAL_P_NC-Pad45)") (class "Default")
      (node (ref "U1") (pin "45") (pinfunction "XTAL_P_NC_45") (pintype "passive+no_connect"))
    )
    (net (code "68") (name "unconnected-(U3-NC-Pad4)") (class "Default")
      (node (ref "U3") (pin "4") (pinfunction "NC_4") (pintype "passive+no_connect"))
    )
    (net (code "69") (name "unconnected-(U4-OUT-Pad3)") (class "Default")
      (node (ref "U4") (pin "3") (pinfunction "OUT_3") (pintype "passive+no_connect"))
    )
  )
)
